# Sheet1.net
KiCad netlist of a schematic drawn in Altium Designer
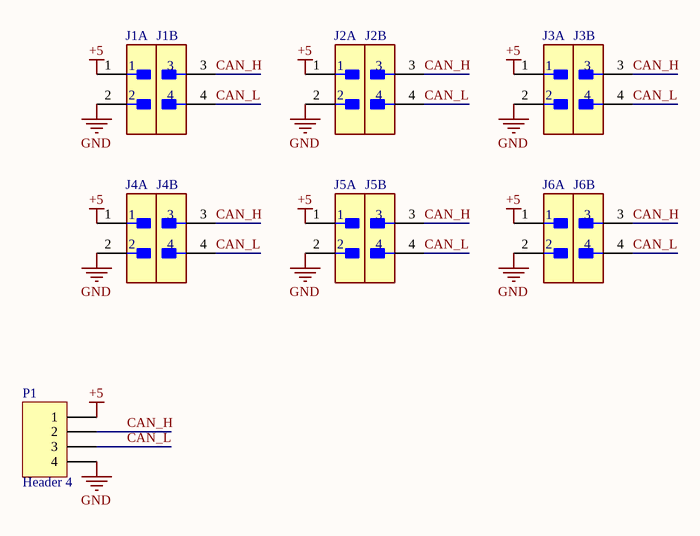
[diagram p0: Sheet1.SchDoc]

(export (version "E")
  (design (tool "Eeschema 10.0.6"))
  (components
    (comp (ref "J1")
      (value "43045-0427")
      (footprint "FP-43045-0427-MFG")
      (description "CONN HEADER VERT 4POS 3MM")
      (libsource (lib "") (part "ac72c5313ea981db199dbd0e8237b04_1"))
    )
    (comp (ref "J2")
      (value "43045-0427")
      (footprint "FP-43045-0427-MFG")
      (description "CONN HEADER VERT 4POS 3MM")
      (libsource (lib "") (part "ac72c5313ea981db199dbd0e8237b04_1"))
    )
    (comp (ref "J3")
      (value "43045-0427")
      (footprint "FP-43045-0427-MFG")
      (description "CONN HEADER VERT 4POS 3MM")
      (libsource (lib "Altium Content Vault") (part "ac72c5313ea981db199dbd0e8237b04"))
    )
    (comp (ref "J4")
      (value "43045-0427")
      (footprint "FP-43045-0427-MFG")
      (description "CONN HEADER VERT 4POS 3MM")
      (libsource (lib "") (part "ac72c5313ea981db199dbd0e8237b04_1"))
    )
    (comp (ref "J5")
      (value "43045-0427")
      (footprint "FP-43045-0427-MFG")
      (description "CONN HEADER VERT 4POS 3MM")
      (libsource (lib "Altium Content Vault") (part "ac72c5313ea981db199dbd0e8237b04"))
    )
    (comp (ref "J6")
      (value "43045-0427")
      (footprint "FP-43045-0427-MFG")
      (description "CONN HEADER VERT 4POS 3MM")
      (libsource (lib "") (part "ac72c5313ea981db199dbd0e8237b04_1"))
    )
    (comp (ref "P1")
      (value "Header 4")
      (footprint "HDR1X4")
      (description "Header, 4-Pin")
      (fields (field (name "PUBLISHER") "Altium Limited"))
      (libsource (lib "Miscellaneous Connectors") (part "Header 4"))
    )
  )
  (nets
    (net (code "1") (name "+5") (class "Default")
      (node (ref "J1") (pin "1") (pinfunction "1_1") (pintype "passive"))
      (node (ref "J2") (pin "1") (pinfunction "1_1") (pintype "passive"))
      (node (ref "J3") (pin "1") (pinfunction "1_1") (pintype "passive"))
      (node (ref "J4") (pin "1") (pinfunction "1_1") (pintype "passive"))
      (node (ref "J5") (pin "1") (pinfunction "1_1") (pintype "passive"))
      (node (ref "J6") (pin "1") (pinfunction "1_1") (pintype "passive"))
      (node (ref "P1") (pin "1") (pinfunction "1_1") (pintype "passive"))
    )
    (net (code "2") (name "/CAN_H") (class "Default")
      (node (ref "J1") (pin "3") (pinfunction "3_3") (pintype "passive"))
      (node (ref "J2") (pin "3") (pinfunction "3_3") (pintype "passive"))
      (node (ref "J3") (pin "3") (pinfunction "3_3") (pintype "passive"))
      (node (ref "J4") (pin "3") (pinfunction "3_3") (pintype "passive"))
      (node (ref "J5") (pin "3") (pinfunction "3_3") (pintype "passive"))
      (node (ref "J6") (pin "3") (pinfunction "3_3") (pintype "passive"))
      (node (ref "P1") (pin "2") (pinfunction "2_2") (pintype "passive"))
    )
    (net (code "3") (name "/CAN_L") (class "Default")
      (node (ref "J1") (pin "4") (pinfunction "4_4") (pintype "passive"))
      (node (ref "J2") (pin "4") (pinfunction "4_4") (pintype "passive"))
      (node (ref "J3") (pin "4") (pinfunction "4_4") (pintype "passive"))
      (node (ref "J4") (pin "4") (pinfunction "4_4") (pintype "passive"))
      (node (ref "J5") (pin "4") (pinfunction "4_4") (pintype "passive"))
      (node (ref "J6") (pin "4") (pinfunction "4_4") (pintype "passive"))
      (node (ref "P1") (pin "3") (pinfunction "3_3") (pintype "passive"))
    )
    (net (code "4") (name "GND") (class "Default")
      (node (ref "J1") (pin "2") (pinfunction "2_2") (pintype "passive"))
      (node (ref "J2") (pin "2") (pinfunction "2_2") (pintype "passive"))
      (node (ref "J3") (pin "2") (pinfunction "2_2") (pintype "passive"))
      (node (ref "J4") (pin "2") (pinfunction "2_2") (pintype "passive"))
      (node (ref "J5") (pin "2") (pinfunction "2_2") (pintype "passive"))
      (node (ref "J6") (pin "2") (pinfunction "2_2") (pintype "passive"))
      (node (ref "P1") (pin "4") (pinfunction "4_4") (pintype "passive"))
    )
  )
)
